# imu.net
KiCad netlist of a schematic drawn in EAGLE
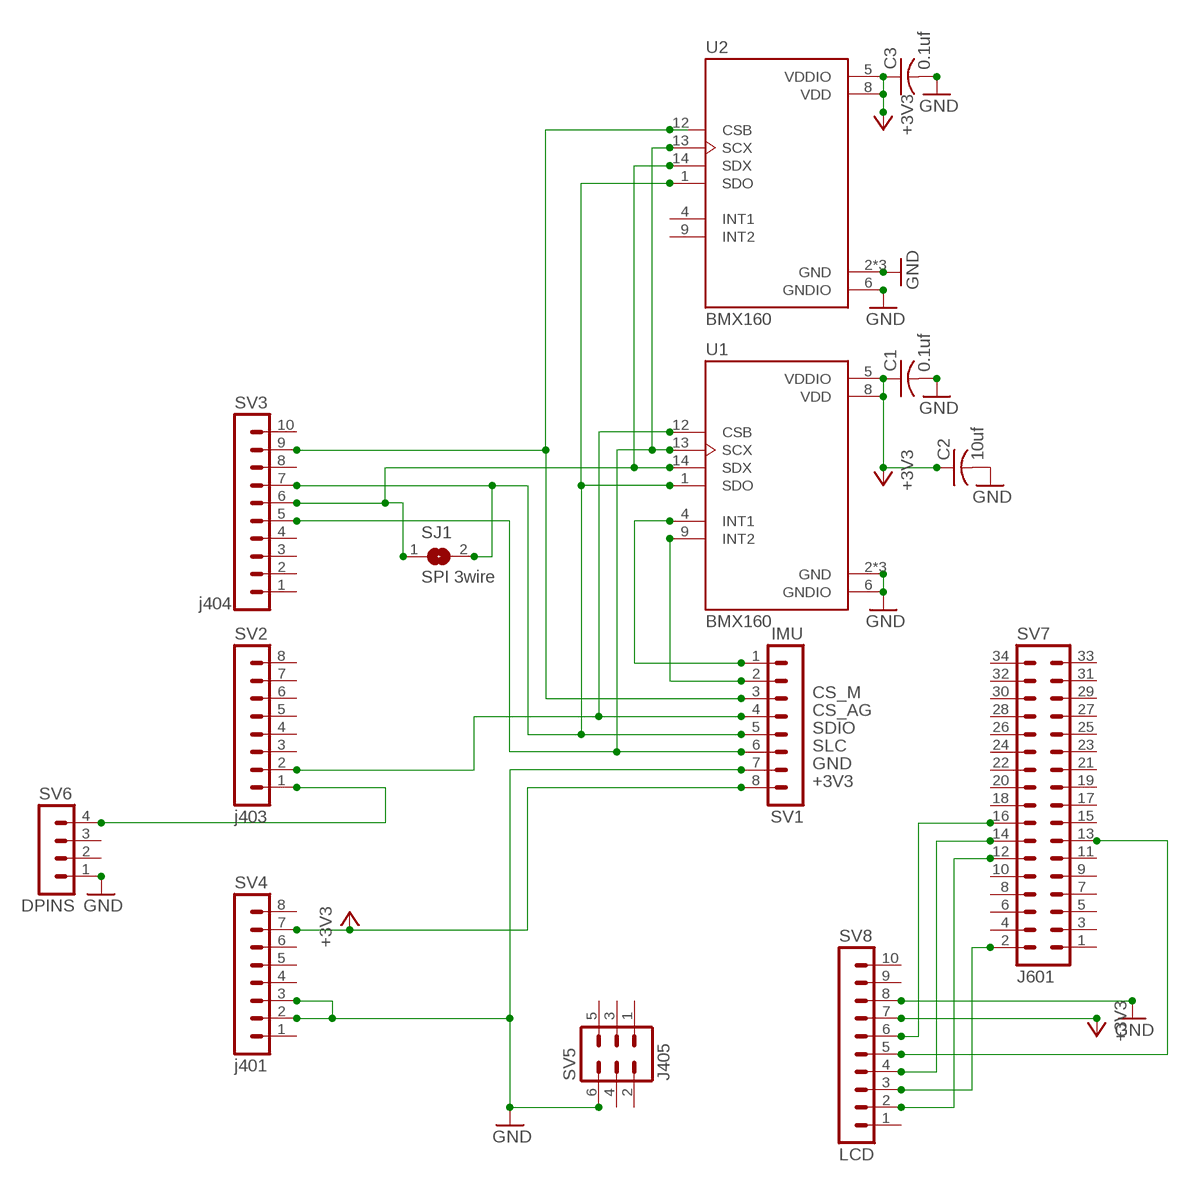
[diagram p0: schematic, sheet 1]

(export (version "E")
  (design (tool "Eeschema 10.0.6"))
  (components
    (comp (ref "C1")
      (value "0.1uf")
      (footprint "eagle-import:C0805")
      (libsource (lib "eagle-import") (part "C-USC0805"))
    )
    (comp (ref "C2")
      (value "10uf")
      (footprint "eagle-import:C0805")
      (libsource (lib "eagle-import") (part "C-USC0805"))
    )
    (comp (ref "C3")
      (value "0.1uf")
      (footprint "eagle-import:C0805")
      (libsource (lib "eagle-import") (part "C-USC0805"))
    )
    (comp (ref "SJ1")
      (value "SPI 3wire")
      (footprint "eagle-import:SJ")
      (libsource (lib "eagle-import") (part "SJ"))
    )
    (comp (ref "SV1")
      (value "IMU")
      (footprint "eagle-import:MA08-1")
      (libsource (lib "eagle-import") (part "MA08-1"))
    )
    (comp (ref "SV2")
      (value "j403")
      (footprint "eagle-import:MA08-1")
      (libsource (lib "eagle-import") (part "MA08-1"))
    )
    (comp (ref "SV3")
      (value "j404")
      (footprint "eagle-import:MA10-1")
      (libsource (lib "eagle-import") (part "MA10-1"))
    )
    (comp (ref "SV4")
      (value "j401")
      (footprint "eagle-import:MA08-1")
      (libsource (lib "eagle-import") (part "MA08-1"))
    )
    (comp (ref "SV5")
      (value "J405")
      (footprint "eagle-import:MA03-2")
      (libsource (lib "eagle-import") (part "MA03-2"))
    )
    (comp (ref "SV6")
      (value "DPINS")
      (footprint "eagle-import:MA04-1")
      (libsource (lib "eagle-import") (part "MA04-1"))
    )
    (comp (ref "SV7")
      (value "J601")
      (footprint "eagle-import:MA17-2W")
      (libsource (lib "eagle-import") (part "MA17-2W"))
    )
    (comp (ref "SV8")
      (value "LCD")
      (footprint "eagle-import:MA10-1")
      (libsource (lib "eagle-import") (part "MA10-1"))
    )
    (comp (ref "U1")
      (value "BMX160")
      (footprint "eagle-import:PQFN50P250X300X100-14N")
      (fields (field (name "MF") "Bosch Sensortec"))
      (libsource (lib "eagle-import") (part "BMX160"))
    )
    (comp (ref "U2")
      (value "BMX160")
      (footprint "eagle-import:PQFN50P250X300X100-14N")
      (fields (field (name "MF") "Bosch Sensortec"))
      (libsource (lib "eagle-import") (part "BMX160"))
    )
  )
  (nets
    (net (code "1") (name "+3V3") (class "Default")
      (node (ref "C1") (pin "1") (pinfunction "1_1") (pintype "passive"))
      (node (ref "C2") (pin "1") (pinfunction "1_1") (pintype "passive"))
      (node (ref "C3") (pin "1") (pinfunction "1_1") (pintype "passive"))
      (node (ref "SV1") (pin "8") (pinfunction "8_8") (pintype "passive"))
      (node (ref "SV4") (pin "7") (pinfunction "7_7") (pintype "passive"))
      (node (ref "SV8") (pin "7") (pinfunction "7_7") (pintype "passive"))
      (node (ref "U1") (pin "5") (pinfunction "VDDIO_5") (pintype "power_in"))
      (node (ref "U1") (pin "8") (pinfunction "VDD_8") (pintype "power_in"))
      (node (ref "U2") (pin "5") (pinfunction "VDDIO_5") (pintype "power_in"))
      (node (ref "U2") (pin "8") (pinfunction "VDD_8") (pintype "power_in"))
    )
    (net (code "2") (name "/CS_AG") (class "Default")
      (node (ref "SV1") (pin "4") (pinfunction "4_4") (pintype "passive"))
      (node (ref "SV2") (pin "2") (pinfunction "2_2") (pintype "passive"))
      (node (ref "U1") (pin "12") (pinfunction "CSB_12") (pintype "input"))
    )
    (net (code "3") (name "/CS_M") (class "Default")
      (node (ref "SV1") (pin "3") (pinfunction "3_3") (pintype "passive"))
      (node (ref "SV3") (pin "9") (pinfunction "9_9") (pintype "passive"))
      (node (ref "U2") (pin "12") (pinfunction "CSB_12") (pintype "input"))
    )
    (net (code "4") (name "/SDIO") (class "Default")
      (node (ref "SJ1") (pin "2") (pinfunction "2_2") (pintype "passive"))
      (node (ref "SV1") (pin "5") (pinfunction "5_5") (pintype "passive"))
      (node (ref "SV3") (pin "7") (pinfunction "7_7") (pintype "passive"))
      (node (ref "U1") (pin "1") (pinfunction "SDO_1") (pintype "bidirectional"))
      (node (ref "U2") (pin "1") (pinfunction "SDO_1") (pintype "bidirectional"))
    )
    (net (code "5") (name "/SLC") (class "Default")
      (node (ref "SV1") (pin "6") (pinfunction "6_6") (pintype "passive"))
      (node (ref "SV3") (pin "5") (pinfunction "5_5") (pintype "passive"))
      (node (ref "U1") (pin "13") (pinfunction "SCX_13") (pintype "input"))
      (node (ref "U2") (pin "13") (pinfunction "SCX_13") (pintype "input"))
    )
    (net (code "6") (name "GND") (class "Default")
      (node (ref "C1") (pin "2") (pinfunction "2_2") (pintype "passive"))
      (node (ref "C2") (pin "2") (pinfunction "2_2") (pintype "passive"))
      (node (ref "C3") (pin "2") (pinfunction "2_2") (pintype "passive"))
      (node (ref "SV1") (pin "7") (pinfunction "7_7") (pintype "passive"))
      (node (ref "SV4") (pin "2") (pinfunction "2_2") (pintype "passive"))
      (node (ref "SV4") (pin "3") (pinfunction "3_3") (pintype "passive"))
      (node (ref "SV5") (pin "6") (pinfunction "6_6") (pintype "passive"))
      (node (ref "SV6") (pin "1") (pinfunction "1_1") (pintype "passive"))
      (node (ref "SV8") (pin "8") (pinfunction "8_8") (pintype "passive"))
      (node (ref "U1") (pin "2") (pinfunction "GND_2") (pintype "power_in"))
      (node (ref "U1") (pin "3") (pinfunction "GND_3") (pintype "power_in"))
      (node (ref "U1") (pin "6") (pinfunction "GNDIO_6") (pintype "power_in"))
      (node (ref "U1") (pin "7") (pinfunction "GND_7") (pintype "power_in"))
      (node (ref "U2") (pin "2") (pinfunction "GND_2") (pintype "power_in"))
      (node (ref "U2") (pin "3") (pinfunction "GND_3") (pintype "power_in"))
      (node (ref "U2") (pin "6") (pinfunction "GNDIO_6") (pintype "power_in"))
      (node (ref "U2") (pin "7") (pinfunction "GND_7") (pintype "power_in"))
    )
    (net (code "7") (name "Net-(SV2-Pad1)") (class "Default")
      (node (ref "SV2") (pin "1") (pinfunction "1_1") (pintype "passive"))
      (node (ref "SV6") (pin "4") (pinfunction "4_4") (pintype "passive"))
    )
    (net (code "8") (name "Net-(SV7-Pad2)") (class "Default")
      (node (ref "SV7") (pin "2") (pinfunction "2_2") (pintype "passive"))
      (node (ref "SV8") (pin "3") (pinfunction "3_3") (pintype "passive"))
    )
    (net (code "9") (name "Net-(SV7-Pad12)") (class "Default")
      (node (ref "SV7") (pin "12") (pinfunction "12_12") (pintype "passive"))
      (node (ref "SV8") (pin "2") (pinfunction "2_2") (pintype "passive"))
    )
    (net (code "10") (name "Net-(SV7-Pad13)") (class "Default")
      (node (ref "SV7") (pin "13") (pinfunction "13_13") (pintype "passive"))
      (node (ref "SV8") (pin "5") (pinfunction "5_5") (pintype "passive"))
    )
    (net (code "11") (name "Net-(SV7-Pad14)") (class "Default")
      (node (ref "SV7") (pin "14") (pinfunction "14_14") (pintype "passive"))
      (node (ref "SV8") (pin "4") (pinfunction "4_4") (pintype "passive"))
    )
    (net (code "12") (name "Net-(SV7-Pad16)") (class "Default")
      (node (ref "SV7") (pin "16") (pinfunction "16_16") (pintype "passive"))
      (node (ref "SV8") (pin "6") (pinfunction "6_6") (pintype "passive"))
    )
    (net (code "13") (name "Net-(U1-INT1)") (class "Default")
      (node (ref "SV1") (pin "1") (pinfunction "1_1") (pintype "passive"))
      (node (ref "U1") (pin "4") (pinfunction "INT1_4") (pintype "bidirectional"))
    )
    (net (code "14") (name "Net-(U1-INT2)") (class "Default")
      (node (ref "SV1") (pin "2") (pinfunction "2_2") (pintype "passive"))
      (node (ref "U1") (pin "9") (pinfunction "INT2_9") (pintype "bidirectional"))
    )
    (net (code "15") (name "Net-(U1-SDX)") (class "Default")
      (node (ref "SJ1") (pin "1") (pinfunction "1_1") (pintype "passive"))
      (node (ref "SV3") (pin "6") (pinfunction "6_6") (pintype "passive"))
      (node (ref "U1") (pin "14") (pinfunction "SDX_14") (pintype "bidirectional"))
      (node (ref "U2") (pin "14") (pinfunction "SDX_14") (pintype "bidirectional"))
    )
    (net (code "16") (name "unconnected-(SV2-Pad3)") (class "Default")
      (node (ref "SV2") (pin "3") (pinfunction "3_3") (pintype "passive"))
    )
    (net (code "17") (name "unconnected-(SV2-Pad4)") (class "Default")
      (node (ref "SV2") (pin "4") (pinfunction "4_4") (pintype "passive"))
    )
    (net (code "18") (name "unconnected-(SV2-Pad5)") (class "Default")
      (node (ref "SV2") (pin "5") (pinfunction "5_5") (pintype "passive"))
    )
    (net (code "19") (name "unconnected-(SV2-Pad6)") (class "Default")
      (node (ref "SV2") (pin "6") (pinfunction "6_6") (pintype "passive"))
    )
    (net (code "20") (name "unconnected-(SV2-Pad7)") (class "Default")
      (node (ref "SV2") (pin "7") (pinfunction "7_7") (pintype "passive"))
    )
    (net (code "21") (name "unconnected-(SV2-Pad8)") (class "Default")
      (node (ref "SV2") (pin "8") (pinfunction "8_8") (pintype "passive"))
    )
    (net (code "22") (name "unconnected-(SV3-Pad1)") (class "Default")
      (node (ref "SV3") (pin "1") (pinfunction "1_1") (pintype "passive"))
    )
    (net (code "23") (name "unconnected-(SV3-Pad2)") (class "Default")
      (node (ref "SV3") (pin "2") (pinfunction "2_2") (pintype "passive"))
    )
    (net (code "24") (name "unconnected-(SV3-Pad3)") (class "Default")
      (node (ref "SV3") (pin "3") (pinfunction "3_3") (pintype "passive"))
    )
    (net (code "25") (name "unconnected-(SV3-Pad4)") (class "Default")
      (node (ref "SV3") (pin "4") (pinfunction "4_4") (pintype "passive"))
    )
    (net (code "26") (name "unconnected-(SV3-Pad8)") (class "Default")
      (node (ref "SV3") (pin "8") (pinfunction "8_8") (pintype "passive"))
    )
    (net (code "27") (name "unconnected-(SV3-Pad10)") (class "Default")
      (node (ref "SV3") (pin "10") (pinfunction "10_10") (pintype "passive"))
    )
    (net (code "28") (name "unconnected-(SV4-Pad1)") (class "Default")
      (node (ref "SV4") (pin "1") (pinfunction "1_1") (pintype "passive"))
    )
    (net (code "29") (name "unconnected-(SV4-Pad4)") (class "Default")
      (node (ref "SV4") (pin "4") (pinfunction "4_4") (pintype "passive"))
    )
    (net (code "30") (name "unconnected-(SV4-Pad5)") (class "Default")
      (node (ref "SV4") (pin "5") (pinfunction "5_5") (pintype "passive"))
    )
    (net (code "31") (name "unconnected-(SV4-Pad6)") (class "Default")
      (node (ref "SV4") (pin "6") (pinfunction "6_6") (pintype "passive"))
    )
    (net (code "32") (name "unconnected-(SV4-Pad8)") (class "Default")
      (node (ref "SV4") (pin "8") (pinfunction "8_8") (pintype "passive"))
    )
    (net (code "33") (name "unconnected-(SV5-Pad1)") (class "Default")
      (node (ref "SV5") (pin "1") (pinfunction "1_1") (pintype "passive"))
    )
    (net (code "34") (name "unconnected-(SV5-Pad2)") (class "Default")
      (node (ref "SV5") (pin "2") (pinfunction "2_2") (pintype "passive"))
    )
    (net (code "35") (name "unconnected-(SV5-Pad3)") (class "Default")
      (node (ref "SV5") (pin "3") (pinfunction "3_3") (pintype "passive"))
    )
    (net (code "36") (name "unconnected-(SV5-Pad4)") (class "Default")
      (node (ref "SV5") (pin "4") (pinfunction "4_4") (pintype "passive"))
    )
    (net (code "37") (name "unconnected-(SV5-Pad5)") (class "Default")
      (node (ref "SV5") (pin "5") (pinfunction "5_5") (pintype "passive"))
    )
    (net (code "38") (name "unconnected-(SV6-Pad2)") (class "Default")
      (node (ref "SV6") (pin "2") (pinfunction "2_2") (pintype "passive"))
    )
    (net (code "39") (name "unconnected-(SV6-Pad3)") (class "Default")
      (node (ref "SV6") (pin "3") (pinfunction "3_3") (pintype "passive"))
    )
    (net (code "40") (name "unconnected-(SV7-Pad1)") (class "Default")
      (node (ref "SV7") (pin "1") (pinfunction "1_1") (pintype "passive"))
    )
    (net (code "41") (name "unconnected-(SV7-Pad3)") (class "Default")
      (node (ref "SV7") (pin "3") (pinfunction "3_3") (pintype "passive"))
    )
    (net (code "42") (name "unconnected-(SV7-Pad4)") (class "Default")
      (node (ref "SV7") (pin "4") (pinfunction "4_4") (pintype "passive"))
    )
    (net (code "43") (name "unconnected-(SV7-Pad5)") (class "Default")
      (node (ref "SV7") (pin "5") (pinfunction "5_5") (pintype "passive"))
    )
    (net (code "44") (name "unconnected-(SV7-Pad6)") (class "Default")
      (node (ref "SV7") (pin "6") (pinfunction "6_6") (pintype "passive"))
    )
    (net (code "45") (name "unconnected-(SV7-Pad7)") (class "Default")
      (node (ref "SV7") (pin "7") (pinfunction "7_7") (pintype "passive"))
    )
    (net (code "46") (name "unconnected-(SV7-Pad8)") (class "Default")
      (node (ref "SV7") (pin "8") (pinfunction "8_8") (pintype "passive"))
    )
    (net (code "47") (name "unconnected-(SV7-Pad9)") (class "Default")
      (node (ref "SV7") (pin "9") (pinfunction "9_9") (pintype "passive"))
    )
    (net (code "48") (name "unconnected-(SV7-Pad10)") (class "Default")
      (node (ref "SV7") (pin "10") (pinfunction "10_10") (pintype "passive"))
    )
    (net (code "49") (name "unconnected-(SV7-Pad11)") (class "Default")
      (node (ref "SV7") (pin "11") (pinfunction "11_11") (pintype "passive"))
    )
    (net (code "50") (name "unconnected-(SV7-Pad15)") (class "Default")
      (node (ref "SV7") (pin "15") (pinfunction "15_15") (pintype "passive"))
    )
    (net (code "51") (name "unconnected-(SV7-Pad17)") (class "Default")
      (node (ref "SV7") (pin "17") (pinfunction "17_17") (pintype "passive"))
    )
    (net (code "52") (name "unconnected-(SV7-Pad18)") (class "Default")
      (node (ref "SV7") (pin "18") (pinfunction "18_18") (pintype "passive"))
    )
    (net (code "53") (name "unconnected-(SV7-Pad19)") (class "Default")
      (node (ref "SV7") (pin "19") (pinfunction "19_19") (pintype "passive"))
    )
    (net (code "54") (name "unconnected-(SV7-Pad20)") (class "Default")
      (node (ref "SV7") (pin "20") (pinfunction "20_20") (pintype "passive"))
    )
    (net (code "55") (name "unconnected-(SV7-Pad21)") (class "Default")
      (node (ref "SV7") (pin "21") (pinfunction "21_21") (pintype "passive"))
    )
    (net (code "56") (name "unconnected-(SV7-Pad22)") (class "Default")
      (node (ref "SV7") (pin "22") (pinfunction "22_22") (pintype "passive"))
    )
    (net (code "57") (name "unconnected-(SV7-Pad23)") (class "Default")
      (node (ref "SV7") (pin "23") (pinfunction "23_23") (pintype "passive"))
    )
    (net (code "58") (name "unconnected-(SV7-Pad24)") (class "Default")
      (node (ref "SV7") (pin "24") (pinfunction "24_24") (pintype "passive"))
    )
    (net (code "59") (name "unconnected-(SV7-Pad25)") (class "Default")
      (node (ref "SV7") (pin "25") (pinfunction "25_25") (pintype "passive"))
    )
    (net (code "60") (name "unconnected-(SV7-Pad26)") (class "Default")
      (node (ref "SV7") (pin "26") (pinfunction "26_26") (pintype "passive"))
    )
    (net (code "61") (name "unconnected-(SV7-Pad27)") (class "Default")
      (node (ref "SV7") (pin "27") (pinfunction "27_27") (pintype "passive"))
    )
    (net (code "62") (name "unconnected-(SV7-Pad28)") (class "Default")
      (node (ref "SV7") (pin "28") (pinfunction "28_28") (pintype "passive"))
    )
    (net (code "63") (name "unconnected-(SV7-Pad29)") (class "Default")
      (node (ref "SV7") (pin "29") (pinfunction "29_29") (pintype "passive"))
    )
    (net (code "64") (name "unconnected-(SV7-Pad30)") (class "Default")
      (node (ref "SV7") (pin "30") (pinfunction "30_30") (pintype "passive"))
    )
    (net (code "65") (name "unconnected-(SV7-Pad31)") (class "Default")
      (node (ref "SV7") (pin "31") (pinfunction "31_31") (pintype "passive"))
    )
    (net (code "66") (name "unconnected-(SV7-Pad32)") (class "Default")
      (node (ref "SV7") (pin "32") (pinfunction "32_32") (pintype "passive"))
    )
    (net (code "67") (name "unconnected-(SV7-Pad33)") (class "Default")
      (node (ref "SV7") (pin "33") (pinfunction "33_33") (pintype "passive"))
    )
    (net (code "68") (name "unconnected-(SV7-Pad34)") (class "Default")
      (node (ref "SV7") (pin "34") (pinfunction "34_34") (pintype "passive"))
    )
    (net (code "69") (name "unconnected-(SV8-Pad1)") (class "Default")
      (node (ref "SV8") (pin "1") (pinfunction "1_1") (pintype "passive"))
    )
    (net (code "70") (name "unconnected-(SV8-Pad9)") (class "Default")
      (node (ref "SV8") (pin "9") (pinfunction "9_9") (pintype "passive"))
    )
    (net (code "71") (name "unconnected-(SV8-Pad10)") (class "Default")
      (node (ref "SV8") (pin "10") (pinfunction "10_10") (pintype "passive"))
    )
    (net (code "72") (name "unconnected-(U2-INT1-Pad4)") (class "Default")
      (node (ref "U2") (pin "4") (pinfunction "INT1_4") (pintype "bidirectional"))
    )
    (net (code "73") (name "unconnected-(U2-INT2-Pad9)") (class "Default")
      (node (ref "U2") (pin "9") (pinfunction "INT2_9") (pintype "bidirectional"))
    )
  )
)
